# vsrm.net
KiCad netlist of a schematic drawn in EAGLE
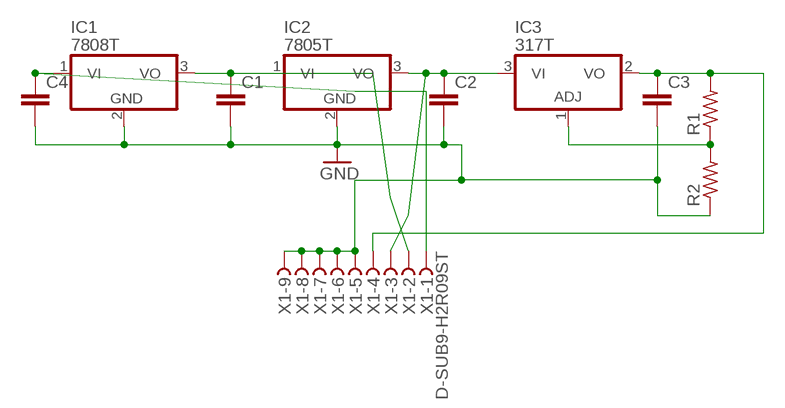
[diagram p0: schematic, sheet 1]

(export (version "E")
  (design (tool "Eeschema 10.0.6"))
  (components
    (comp (ref "C1")
      (value "C2.5/4")
      (footprint "eagle-import:C2.5-4")
      (libsource (lib "eagle-import") (part "C2.5/4"))
    )
    (comp (ref "C2")
      (value "C2.5/4")
      (footprint "eagle-import:C2.5-4")
      (libsource (lib "eagle-import") (part "C2.5/4"))
    )
    (comp (ref "C3")
      (value "C2.5/4")
      (footprint "eagle-import:C2.5-4")
      (libsource (lib "eagle-import") (part "C2.5/4"))
    )
    (comp (ref "C4")
      (value "C2.5/4")
      (footprint "eagle-import:C2.5-4")
      (libsource (lib "eagle-import") (part "C2.5/4"))
    )
    (comp (ref "IC1")
      (value "7808T")
      (footprint "eagle-import:TO220H")
      (libsource (lib "eagle-import") (part "78T08"))
    )
    (comp (ref "IC2")
      (value "7805T")
      (footprint "eagle-import:TO220H")
      (libsource (lib "eagle-import") (part "78T05"))
    )
    (comp (ref "IC3")
      (value "317T")
      (footprint "eagle-import:TO220H")
      (libsource (lib "eagle-import") (part "317T"))
    )
    (comp (ref "R1")
      (value "R-US_0204/7")
      (footprint "eagle-import:0204_7")
      (libsource (lib "eagle-import") (part "R-US_0204/7"))
    )
    (comp (ref "R2")
      (value "R-US_0204/7")
      (footprint "eagle-import:0204_7")
      (libsource (lib "eagle-import") (part "R-US_0204/7"))
    )
    (comp (ref "X1")
      (value "D-SUB9-H2R09ST")
      (footprint "eagle-import:H2R09ST")
      (libsource (lib "eagle-import") (part "D-SUB9-H2R09ST"))
    )
  )
  (nets
    (net (code "1") (name "GND") (class "Default")
      (node (ref "C1") (pin "2") (pinfunction "2_2") (pintype "passive"))
      (node (ref "C2") (pin "2") (pinfunction "2_2") (pintype "passive"))
      (node (ref "C3") (pin "2") (pinfunction "2_2") (pintype "passive"))
      (node (ref "C4") (pin "2") (pinfunction "2_2") (pintype "passive"))
      (node (ref "IC1") (pin "2") (pinfunction "GND_2") (pintype "passive"))
      (node (ref "IC2") (pin "2") (pinfunction "GND_2") (pintype "passive"))
      (node (ref "R2") (pin "1") (pinfunction "1_1") (pintype "passive"))
      (node (ref "X1") (pin "5") (pinfunction "F_5") (pintype "passive"))
      (node (ref "X1") (pin "6") (pinfunction "F_6") (pintype "passive"))
      (node (ref "X1") (pin "7") (pinfunction "F_7") (pintype "passive"))
      (node (ref "X1") (pin "8") (pinfunction "F_8") (pintype "passive"))
      (node (ref "X1") (pin "9") (pinfunction "F_9") (pintype "passive"))
    )
    (net (code "2") (name "Net-(IC1-VI)") (class "Default")
      (node (ref "C4") (pin "1") (pinfunction "1_1") (pintype "passive"))
      (node (ref "IC1") (pin "1") (pinfunction "VI_1") (pintype "input"))
      (node (ref "X1") (pin "1") (pinfunction "F_1") (pintype "passive"))
    )
    (net (code "3") (name "Net-(IC1-VO)") (class "Default")
      (node (ref "C1") (pin "1") (pinfunction "1_1") (pintype "passive"))
      (node (ref "IC1") (pin "3") (pinfunction "VO_3") (pintype "passive"))
      (node (ref "IC2") (pin "1") (pinfunction "VI_1") (pintype "input"))
      (node (ref "X1") (pin "2") (pinfunction "F_2") (pintype "passive"))
    )
    (net (code "4") (name "Net-(IC2-VO)") (class "Default")
      (node (ref "C2") (pin "1") (pinfunction "1_1") (pintype "passive"))
      (node (ref "IC2") (pin "3") (pinfunction "VO_3") (pintype "passive"))
      (node (ref "IC3") (pin "3") (pinfunction "VI_3") (pintype "input"))
      (node (ref "X1") (pin "3") (pinfunction "F_3") (pintype "passive"))
    )
    (net (code "5") (name "Net-(IC3-ADJ)") (class "Default")
      (node (ref "IC3") (pin "1") (pinfunction "ADJ_1") (pintype "input"))
      (node (ref "R1") (pin "1") (pinfunction "1_1") (pintype "passive"))
      (node (ref "R2") (pin "2") (pinfunction "2_2") (pintype "passive"))
    )
    (net (code "6") (name "Net-(IC3-VO)") (class "Default")
      (node (ref "C3") (pin "1") (pinfunction "1_1") (pintype "passive"))
      (node (ref "IC3") (pin "2") (pinfunction "VO_2") (pintype "passive"))
      (node (ref "R1") (pin "2") (pinfunction "2_2") (pintype "passive"))
      (node (ref "X1") (pin "4") (pinfunction "F_4") (pintype "passive"))
    )
  )
)
